# k210-core.net
KiCad netlist of a schematic drawn in Altium Designer
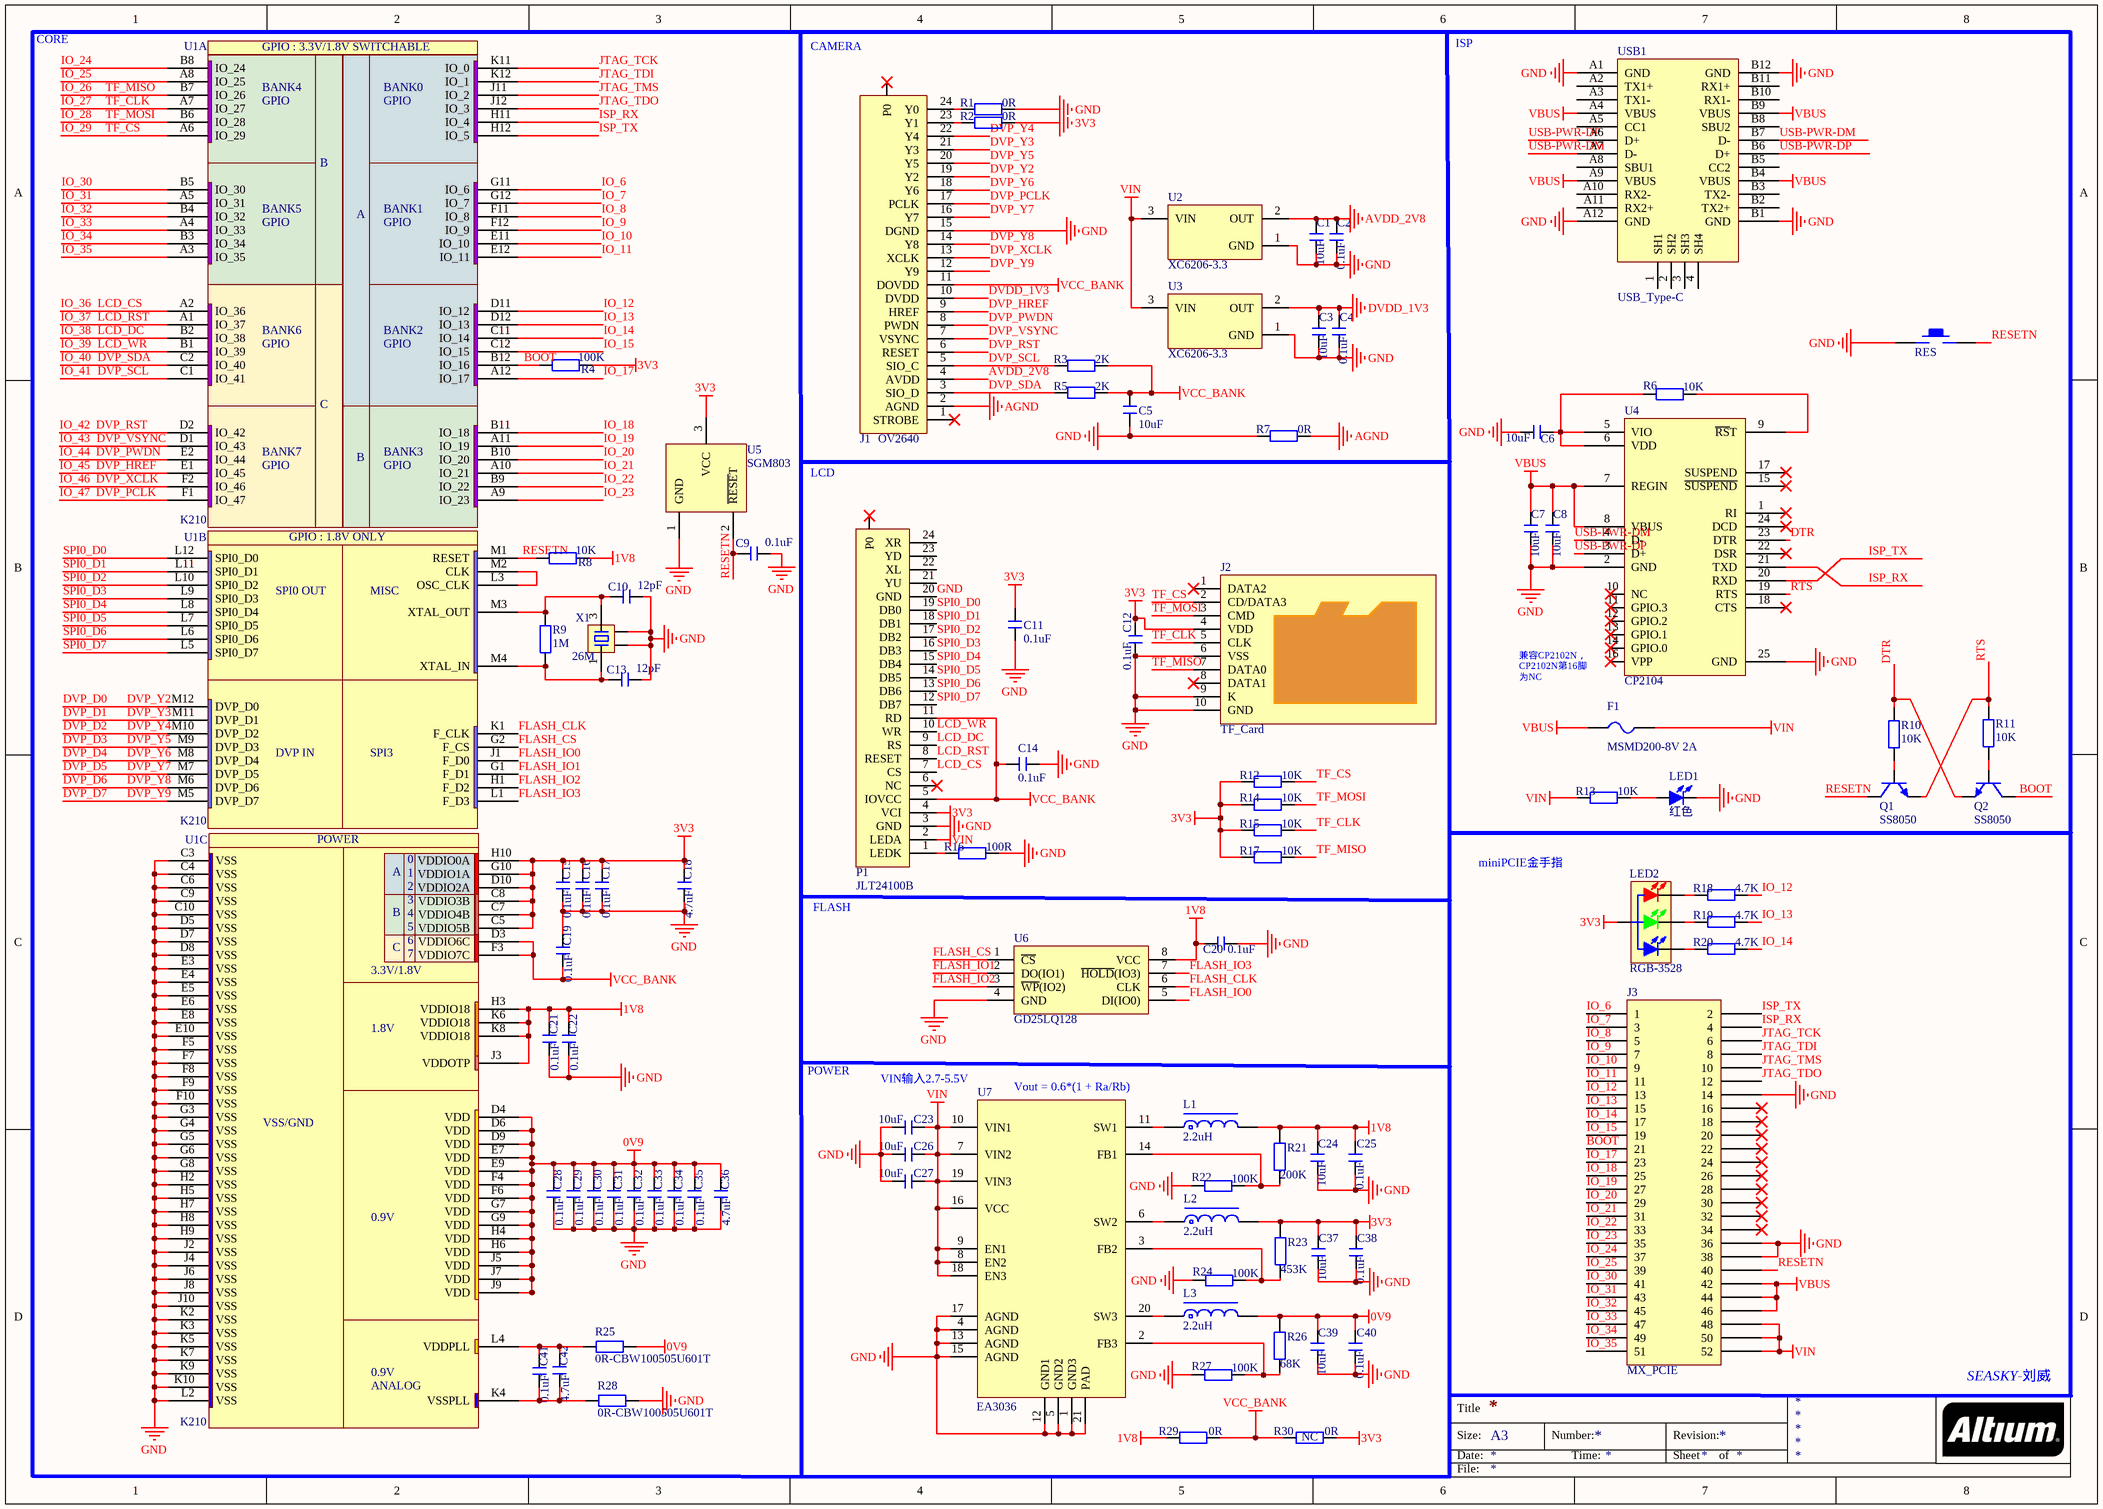
[diagram p0: k210-core.SchDoc]

(export (version "E")
  (design (tool "Eeschema 10.0.6"))
  (components
    (comp (ref "C1")
      (value "10uF")
      (footprint "C 0402_M")
      (description "贴片电容")
      (libsource (lib "0.1 - 电阻-电容-电感") (part "C"))
    )
    (comp (ref "C2")
      (value "0.1uF")
      (footprint "C 0402_M")
      (description "贴片电容")
      (libsource (lib "0.1 - 电阻-电容-电感") (part "C"))
    )
    (comp (ref "C3")
      (value "10uF")
      (footprint "C 0402_M")
      (description "贴片电容")
      (libsource (lib "0.1 - 电阻-电容-电感") (part "C"))
    )
    (comp (ref "C4")
      (value "0.1uF")
      (footprint "C 0402_M")
      (description "贴片电容")
      (libsource (lib "0.1 - 电阻-电容-电感") (part "C"))
    )
    (comp (ref "C5")
      (value "10uF")
      (footprint "C 0402_M")
      (description "贴片电容")
      (libsource (lib "0.1 - 电阻-电容-电感") (part "C"))
    )
    (comp (ref "C6")
      (value "10uF")
      (footprint "C 0402_M")
      (description "贴片电容")
      (libsource (lib "0.1 - 电阻-电容-电感") (part "C"))
    )
    (comp (ref "C7")
      (value "10uF")
      (footprint "C 0402_M")
      (description "贴片电容")
      (libsource (lib "0.1 - 电阻-电容-电感") (part "C"))
    )
    (comp (ref "C8")
      (value "10uF")
      (footprint "C 0402_M")
      (description "贴片电容")
      (libsource (lib "0.1 - 电阻-电容-电感") (part "C"))
    )
    (comp (ref "C9")
      (value "0.1uF")
      (footprint "C 0402_M")
      (description "贴片电容")
      (libsource (lib "0.1 - 电阻-电容-电感") (part "C"))
    )
    (comp (ref "C10")
      (value "12pF")
      (footprint "C 0402_M")
      (description "贴片电容")
      (libsource (lib "0.1 - 电阻-电容-电感") (part "C"))
    )
    (comp (ref "C11")
      (value "0.1uF")
      (footprint "C 0402_M")
      (description "贴片电容")
      (libsource (lib "0.1 - 电阻-电容-电感") (part "C"))
    )
    (comp (ref "C12")
      (value "0.1uF")
      (footprint "C 0402_M")
      (description "贴片电容")
      (libsource (lib "0.1 - 电阻-电容-电感") (part "C"))
    )
    (comp (ref "C13")
      (value "12pF")
      (footprint "C 0402_M")
      (description "贴片电容")
      (libsource (lib "0.1 - 电阻-电容-电感") (part "C"))
    )
    (comp (ref "C14")
      (value "0.1uF")
      (footprint "C 0402_M")
      (description "贴片电容")
      (libsource (lib "0.1 - 电阻-电容-电感") (part "C"))
    )
    (comp (ref "C15")
      (value "0.1uF")
      (footprint "C 0402_M")
      (description "贴片电容")
      (libsource (lib "0.1 - 电阻-电容-电感") (part "C"))
    )
    (comp (ref "C16")
      (value "0.1uF")
      (footprint "C 0402_M")
      (description "贴片电容")
      (libsource (lib "0.1 - 电阻-电容-电感") (part "C"))
    )
    (comp (ref "C17")
      (value "0.1uF")
      (footprint "C 0402_M")
      (description "贴片电容")
      (libsource (lib "0.1 - 电阻-电容-电感") (part "C"))
    )
    (comp (ref "C18")
      (value "4.7uF")
      (footprint "C 0402_M")
      (description "贴片电容")
      (libsource (lib "0.1 - 电阻-电容-电感") (part "C"))
    )
    (comp (ref "C19")
      (value "0.1uF")
      (footprint "C 0402_M")
      (description "贴片电容")
      (libsource (lib "0.1 - 电阻-电容-电感") (part "C"))
    )
    (comp (ref "C20")
      (value "0.1uF")
      (footprint "C 0402_M")
      (description "贴片电容")
      (libsource (lib "0.1 - 电阻-电容-电感") (part "C"))
    )
    (comp (ref "C21")
      (value "0.1uF")
      (footprint "C 0402_M")
      (description "贴片电容")
      (libsource (lib "0.1 - 电阻-电容-电感") (part "C"))
    )
    (comp (ref "C22")
      (value "0.1uF")
      (footprint "C 0402_M")
      (description "贴片电容")
      (libsource (lib "0.1 - 电阻-电容-电感") (part "C"))
    )
    (comp (ref "C23")
      (value "10uF")
      (footprint "C 0402_M")
      (description "贴片电容")
      (libsource (lib "0.1 - 电阻-电容-电感") (part "C"))
    )
    (comp (ref "C24")
      (value "10uF")
      (footprint "C 0402_M")
      (description "贴片电容")
      (libsource (lib "0.1 - 电阻-电容-电感") (part "C"))
    )
    (comp (ref "C25")
      (value "0.1uF")
      (footprint "C 0402_M")
      (description "贴片电容")
      (libsource (lib "0.1 - 电阻-电容-电感") (part "C"))
    )
    (comp (ref "C26")
      (value "10uF")
      (footprint "C 0402_M")
      (description "贴片电容")
      (libsource (lib "0.1 - 电阻-电容-电感") (part "C"))
    )
    (comp (ref "C27")
      (value "10uF")
      (footprint "C 0402_M")
      (description "贴片电容")
      (libsource (lib "0.1 - 电阻-电容-电感") (part "C"))
    )
    (comp (ref "C28")
      (value "0.1uF")
      (footprint "C 0402_M")
      (description "贴片电容")
      (libsource (lib "0.1 - 电阻-电容-电感") (part "C"))
    )
    (comp (ref "C29")
      (value "0.1uF")
      (footprint "C 0402_M")
      (description "贴片电容")
      (libsource (lib "0.1 - 电阻-电容-电感") (part "C"))
    )
    (comp (ref "C30")
      (value "0.1uF")
      (footprint "C 0402_M")
      (description "贴片电容")
      (libsource (lib "0.1 - 电阻-电容-电感") (part "C"))
    )
    (comp (ref "C31")
      (value "0.1uF")
      (footprint "C 0402_M")
      (description "贴片电容")
      (libsource (lib "0.1 - 电阻-电容-电感") (part "C"))
    )
    (comp (ref "C32")
      (value "0.1uF")
      (footprint "C 0402_M")
      (description "贴片电容")
      (libsource (lib "0.1 - 电阻-电容-电感") (part "C"))
    )
    (comp (ref "C33")
      (value "0.1uF")
      (footprint "C 0402_M")
      (description "贴片电容")
      (libsource (lib "0.1 - 电阻-电容-电感") (part "C"))
    )
    (comp (ref "C34")
      (value "0.1uF")
      (footprint "C 0402_M")
      (description "贴片电容")
      (libsource (lib "0.1 - 电阻-电容-电感") (part "C"))
    )
    (comp (ref "C35")
      (value "0.1uF")
      (footprint "C 0402_M")
      (description "贴片电容")
      (libsource (lib "0.1 - 电阻-电容-电感") (part "C"))
    )
    (comp (ref "C36")
      (value "4.7uF")
      (footprint "C 0402_M")
      (description "贴片电容")
      (libsource (lib "0.1 - 电阻-电容-电感") (part "C"))
    )
    (comp (ref "C37")
      (value "10uF")
      (footprint "C 0402_M")
      (description "贴片电容")
      (libsource (lib "0.1 - 电阻-电容-电感") (part "C"))
    )
    (comp (ref "C38")
      (value "0.1uF")
      (footprint "C 0402_M")
      (description "贴片电容")
      (libsource (lib "0.1 - 电阻-电容-电感") (part "C"))
    )
    (comp (ref "C39")
      (value "10uF")
      (footprint "C 0402_M")
      (description "贴片电容")
      (libsource (lib "0.1 - 电阻-电容-电感") (part "C"))
    )
    (comp (ref "C40")
      (value "0.1uF")
      (footprint "C 0402_M")
      (description "贴片电容")
      (libsource (lib "0.1 - 电阻-电容-电感") (part "C"))
    )
    (comp (ref "C41")
      (value "0.1uF")
      (footprint "C 0402_M")
      (description "贴片电容")
      (libsource (lib "0.1 - 电阻-电容-电感") (part "C"))
    )
    (comp (ref "C42")
      (value "4.7uF")
      (footprint "C 0402_M")
      (description "贴片电容")
      (libsource (lib "0.1 - 电阻-电容-电感") (part "C"))
    )
    (comp (ref "F1")
      (value "MSMD200-8V 2A")
      (footprint "FU 1210")
      (description "贴片保险丝")
      (libsource (lib "2.0 - 保险丝-晶振-光耦") (part "FU"))
    )
    (comp (ref "J1")
      (value "OV2640")
      (footprint "FFC/SM0.5-2H24-OV5640")
      (description "Header, 24-Pin")
      (fields (field (name "PUBLISHER") "Altium Limited"))
      (libsource (lib "Vowstar_MCU") (part "OV5640"))
    )
    (comp (ref "J2")
      (value "TF_Card")
      (footprint "TF-SOCKET - short")
      (description "TF卡座")
      (libsource (lib "0.8 - 网口-音频插座") (part "TF_Card"))
    )
    (comp (ref "J3")
      (value "MX_PCIE")
      (footprint "miniPCIE")
      (description "mini-PCI-E")
      (libsource (lib "mx_pcb_library") (part "MX_PCIE"))
    )
    (comp (ref "L1")
      (value "2.2uH")
      (footprint "NR2520")
      (description "NR磁胶电感")
      (libsource (lib "0.1 - 电阻-电容-电感") (part "L-NR"))
    )
    (comp (ref "L2")
      (value "2.2uH")
      (footprint "NR2520")
      (description "NR磁胶电感")
      (libsource (lib "0.1 - 电阻-电容-电感") (part "L-NR"))
    )
    (comp (ref "L3")
      (value "2.2uH")
      (footprint "NR2520")
      (description "NR磁胶电感")
      (libsource (lib "0.1 - 电阻-电容-电感") (part "L-NR"))
    )
    (comp (ref "LED1")
      (value "红色")
      (footprint "LED 0805G")
      (description "贴片LED")
      (libsource (lib "0.3 - LED发光二极管") (part "LED-SMD"))
    )
    (comp (ref "LED2")
      (value "RGB-3528")
      (footprint "LED 3528-4Pin")
      (description "3528三基色LED")
      (libsource (lib "0.3 - LED发光二极管") (part "LED-RGB 3528"))
    )
    (comp (ref "P1")
      (value "JLT24100B")
      (footprint "FFC/SM0.5-2H24-LCD")
      (fields (field (name "PUBLISHER") "Altium Limited"))
      (libsource (lib "Schlib1") (part "JLT24100B"))
    )
    (comp (ref "Q1")
      (value "SS8050")
      (footprint "SOT23-3N")
      (description "高频放大-NPN型")
      (libsource (lib "0.4 - 三极管") (part "8050-SMD"))
    )
    (comp (ref "Q2")
      (value "SS8050")
      (footprint "SOT23-3N")
      (description "高频放大-NPN型")
      (libsource (lib "0.4 - 三极管") (part "8050-SMD"))
    )
    (comp (ref "R1")
      (value "0R")
      (footprint "R 0402_M")
      (description "贴片电阻")
      (libsource (lib "0.1 - 电阻-电容-电感") (part "R"))
    )
    (comp (ref "R2")
      (value "0R")
      (footprint "R 0402_M")
      (description "贴片电阻")
      (libsource (lib "0.1 - 电阻-电容-电感") (part "R"))
    )
    (comp (ref "R3")
      (value "2K")
      (footprint "R 0402_M")
      (description "贴片电阻")
      (libsource (lib "0.1 - 电阻-电容-电感") (part "R"))
    )
    (comp (ref "R4")
      (value "100K")
      (footprint "R 0402_M")
      (description "贴片电阻")
      (libsource (lib "0.1 - 电阻-电容-电感") (part "R"))
    )
    (comp (ref "R5")
      (value "2K")
      (footprint "R 0402_M")
      (description "贴片电阻")
      (libsource (lib "0.1 - 电阻-电容-电感") (part "R"))
    )
    (comp (ref "R6")
      (value "10K")
      (footprint "R 0402_M")
      (description "贴片电阻")
      (libsource (lib "0.1 - 电阻-电容-电感") (part "R"))
    )
    (comp (ref "R7")
      (value "0R")
      (footprint "R 0402_M")
      (description "贴片电阻")
      (libsource (lib "0.1 - 电阻-电容-电感") (part "R"))
    )
    (comp (ref "R8")
      (value "10K")
      (footprint "R 0402_M")
      (description "贴片电阻")
      (libsource (lib "0.1 - 电阻-电容-电感") (part "R"))
    )
    (comp (ref "R9")
      (value "1M")
      (footprint "R 0402_M")
      (description "贴片电阻")
      (libsource (lib "0.1 - 电阻-电容-电感") (part "R"))
    )
    (comp (ref "R10")
      (value "10K")
      (footprint "R 0402_M")
      (description "贴片电阻")
      (libsource (lib "0.1 - 电阻-电容-电感") (part "R"))
    )
    (comp (ref "R11")
      (value "10K")
      (footprint "R 0402_M")
      (description "贴片电阻")
      (libsource (lib "0.1 - 电阻-电容-电感") (part "R"))
    )
    (comp (ref "R12")
      (value "10K")
      (footprint "R 0402_M")
      (description "贴片电阻")
      (libsource (lib "0.1 - 电阻-电容-电感") (part "R"))
    )
    (comp (ref "R13")
      (value "10K")
      (footprint "R 0402_M")
      (description "贴片电阻")
      (libsource (lib "0.1 - 电阻-电容-电感") (part "R"))
    )
    (comp (ref "R14")
      (value "10K")
      (footprint "R 0402_M")
      (description "贴片电阻")
      (libsource (lib "0.1 - 电阻-电容-电感") (part "R"))
    )
    (comp (ref "R15")
      (value "10K")
      (footprint "R 0402_M")
      (description "贴片电阻")
      (libsource (lib "0.1 - 电阻-电容-电感") (part "R"))
    )
    (comp (ref "R16")
      (value "100R")
      (footprint "R 0402_M")
      (description "贴片电阻")
      (libsource (lib "0.1 - 电阻-电容-电感") (part "R"))
    )
    (comp (ref "R17")
      (value "10K")
      (footprint "R 0402_M")
      (description "贴片电阻")
      (libsource (lib "0.1 - 电阻-电容-电感") (part "R"))
    )
    (comp (ref "R18")
      (value "4.7K")
      (footprint "R 0402_M")
      (description "贴片电阻")
      (libsource (lib "0.1 - 电阻-电容-电感") (part "R"))
    )
    (comp (ref "R19")
      (value "4.7K")
      (footprint "R 0402_M")
      (description "贴片电阻")
      (libsource (lib "0.1 - 电阻-电容-电感") (part "R"))
    )
    (comp (ref "R20")
      (value "4.7K")
      (footprint "R 0402_M")
      (description "贴片电阻")
      (libsource (lib "0.1 - 电阻-电容-电感") (part "R"))
    )
    (comp (ref "R21")
      (value "200K")
      (footprint "R 0402_M")
      (description "贴片电阻")
      (libsource (lib "0.1 - 电阻-电容-电感") (part "R"))
    )
    (comp (ref "R22")
      (value "100K")
      (footprint "R 0402_M")
      (description "贴片电阻")
      (libsource (lib "0.1 - 电阻-电容-电感") (part "R"))
    )
    (comp (ref "R23")
      (value "453K")
      (footprint "R 0402_M")
      (description "贴片电阻")
      (libsource (lib "0.1 - 电阻-电容-电感") (part "R"))
    )
    (comp (ref "R24")
      (value "100K")
      (footprint "R 0402_M")
      (description "贴片电阻")
      (libsource (lib "0.1 - 电阻-电容-电感") (part "R"))
    )
    (comp (ref "R25")
      (value "0R-CBW100505U601T")
      (footprint "R 0402_M")
      (description "贴片电阻")
      (libsource (lib "0.1 - 电阻-电容-电感") (part "R"))
    )
    (comp (ref "R26")
      (value "68K")
      (footprint "R 0402_M")
      (description "贴片电阻")
      (libsource (lib "0.1 - 电阻-电容-电感") (part "R"))
    )
    (comp (ref "R27")
      (value "100K")
      (footprint "R 0402_M")
      (description "贴片电阻")
      (libsource (lib "0.1 - 电阻-电容-电感") (part "R"))
    )
    (comp (ref "R28")
      (value "0R-CBW100505U601T")
      (footprint "R 0402_M")
      (description "贴片电阻")
      (libsource (lib "0.1 - 电阻-电容-电感") (part "R"))
    )
    (comp (ref "R29")
      (value "0R")
      (footprint "R 0402_M")
      (description "贴片电阻")
      (libsource (lib "0.1 - 电阻-电容-电感") (part "R"))
    )
    (comp (ref "R30")
      (value "0R")
      (footprint "R 0402_M")
      (description "贴片电阻")
      (libsource (lib "0.1 - 电阻-电容-电感") (part "R"))
    )
    (comp (ref "RST1")
      (value "RES")
      (footprint "mx_pcb_library:SMD-3.2*4.2")
      (libsource (lib "mx_pcb_library") (part "KEY_M"))
    )
    (comp (ref "U1")
      (value "K210")
      (footprint "BGA144C65P12X12_800X800X95")
      (description "Canaan Kendryte K210 AI SoC")
      (libsource (lib "Vowstar_MCU") (part "K210"))
    )
    (comp (ref "U2")
      (value "XC6206-3.3")
      (footprint "2.07-SOT封装:SOT23-3N")
      (description "SOT-23,XC6206P332MR,MAX8V,100mA")
      (libsource (lib "1.1 - 电源类芯片") (part "XC6206-3.3"))
    )
    (comp (ref "U3")
      (value "XC6206-3.3")
      (footprint "2.07-SOT封装:SOT23-3N")
      (description "SOT-23,XC6206P332MR,MAX8V,100mA")
      (libsource (lib "1.1 - 电源类芯片") (part "XC6206-3.3"))
    )
    (comp (ref "U4")
      (value "CP2104")
      (footprint "QFN-24_L4.0-W4.0-P0.50-BL-EP2.8")
      (libsource (lib "Vowstar_MCU") (part "CP2104"))
    )
    (comp (ref "U5")
      (value "SGM803")
      (footprint "2.07-SOT封装:SOT23-3N")
      (libsource (lib "Vowstar_MCU") (part "SGM803"))
    )
    (comp (ref "U6")
      (value "GD25LQ128")
      (footprint "WSON-8_L8.0-W6.10-P1.27-BL-EP")
      (description "WSON-8")
      (libsource (lib "Vowstar_MCU") (part "GD25LQ128"))
    )
    (comp (ref "U7")
      (value "EA3036")
      (footprint "QFN20_40P300X300X80_HS-21N")
      (libsource (lib "Vowstar_MCU") (part "EA3036"))
    )
    (comp (ref "USB1")
      (value "USB_Type-C")
      (footprint "Type-C-TOP")
      (libsource (lib "Vowstar_MCU") (part "USB_Type-C"))
    )
    (comp (ref "X1")
      (value "26M")
      (footprint "OSC 3225-4P")
      (description "4脚无源晶振")
      (libsource (lib "2.0 - 保险丝-晶振-光耦") (part "XTAL-4P"))
    )
  )
  (nets
    (net (code "1") (name "/BOOT") (class "Default")
      (node (ref "J3") (pin "21") (pinfunction "21_21") (pintype "passive"))
      (node (ref "Q2") (pin "3") (pinfunction "C_3") (pintype "passive"))
      (node (ref "R4") (pin "1") (pinfunction "1_1") (pintype "passive"))
      (node (ref "U1") (pin "B12") (pinfunction "IO_16_B12") (pintype "passive"))
    )
    (net (code "2") (name "/DTR") (class "Default")
      (node (ref "Q2") (pin "2") (pinfunction "E_2") (pintype "passive"))
      (node (ref "R10") (pin "1") (pinfunction "1_1") (pintype "passive"))
      (node (ref "U4") (pin "23") (pinfunction "DTR_23") (pintype "passive"))
    )
    (net (code "3") (name "/DVP_D0") (class "Default")
      (node (ref "J1") (pin "19") (pinfunction "Y2_19") (pintype "passive"))
      (node (ref "U1") (pin "M12") (pinfunction "DVP_D0_M12") (pintype "passive"))
    )
    (net (code "4") (name "/DVP_D1") (class "Default")
      (node (ref "J1") (pin "21") (pinfunction "Y3_21") (pintype "passive"))
      (node (ref "U1") (pin "M11") (pinfunction "DVP_D1_M11") (pintype "passive"))
    )
    (net (code "5") (name "/DVP_D2") (class "Default")
      (node (ref "J1") (pin "22") (pinfunction "Y4_22") (pintype "passive"))
      (node (ref "U1") (pin "M10") (pinfunction "DVP_D2_M10") (pintype "passive"))
    )
    (net (code "6") (name "/DVP_D3") (class "Default")
      (node (ref "J1") (pin "20") (pinfunction "Y5_20") (pintype "passive"))
      (node (ref "U1") (pin "M9") (pinfunction "DVP_D3_M9") (pintype "passive"))
    )
    (net (code "7") (name "/DVP_D4") (class "Default")
      (node (ref "J1") (pin "18") (pinfunction "Y6_18") (pintype "passive"))
      (node (ref "U1") (pin "M8") (pinfunction "DVP_D4_M8") (pintype "passive"))
    )
    (net (code "8") (name "/DVP_D5") (class "Default")
      (node (ref "J1") (pin "16") (pinfunction "Y7_16") (pintype "passive"))
      (node (ref "U1") (pin "M7") (pinfunction "DVP_D5_M7") (pintype "passive"))
    )
    (net (code "9") (name "/DVP_D6") (class "Default")
      (node (ref "J1") (pin "14") (pinfunction "Y8_14") (pintype "passive"))
      (node (ref "U1") (pin "M6") (pinfunction "DVP_D6_M6") (pintype "passive"))
    )
    (net (code "10") (name "/DVP_D7") (class "Default")
      (node (ref "J1") (pin "12") (pinfunction "Y9_12") (pintype "passive"))
      (node (ref "U1") (pin "M5") (pinfunction "DVP_D7_M5") (pintype "passive"))
    )
    (net (code "11") (name "/DVP_HREF") (class "Default")
      (node (ref "J1") (pin "9") (pinfunction "HREF_9") (pintype "passive"))
      (node (ref "U1") (pin "E1") (pinfunction "IO_45_E1") (pintype "passive"))
    )
    (net (code "12") (name "/DVP_PCLK") (class "Default")
      (node (ref "J1") (pin "17") (pinfunction "PCLK_17") (pintype "passive"))
      (node (ref "U1") (pin "F1") (pinfunction "IO_47_F1") (pintype "passive"))
    )
    (net (code "13") (name "/DVP_PWDN") (class "Default")
      (node (ref "J1") (pin "8") (pinfunction "PWDN_8") (pintype "passive"))
      (node (ref "U1") (pin "E2") (pinfunction "IO_44_E2") (pintype "passive"))
    )
    (net (code "14") (name "/DVP_RST") (class "Default")
      (node (ref "J1") (pin "6") (pinfunction "RESET_6") (pintype "passive"))
      (node (ref "U1") (pin "D2") (pinfunction "IO_42_D2") (pintype "passive"))
    )
    (net (code "15") (name "/DVP_SCL") (class "Default")
      (node (ref "J1") (pin "5") (pinfunction "SIO_C_5") (pintype "passive"))
      (node (ref "R3") (pin "1") (pinfunction "1_1") (pintype "passive"))
      (node (ref "U1") (pin "C1") (pinfunction "IO_41_C1") (pintype "passive"))
    )
    (net (code "16") (name "/DVP_SDA") (class "Default")
      (node (ref "J1") (pin "3") (pinfunction "SIO_D_3") (pintype "passive"))
      (node (ref "R5") (pin "1") (pinfunction "1_1") (pintype "passive"))
      (node (ref "U1") (pin "C2") (pinfunction "IO_40_C2") (pintype "passive"))
    )
    (net (code "17") (name "/DVP_VSYNC") (class "Default")
      (node (ref "J1") (pin "7") (pinfunction "VSYNC_7") (pintype "passive"))
      (node (ref "U1") (pin "D1") (pinfunction "IO_43_D1") (pintype "passive"))
    )
    (net (code "18") (name "/DVP_XCLK") (class "Default")
      (node (ref "J1") (pin "13") (pinfunction "XCLK_13") (pintype "passive"))
      (node (ref "U1") (pin "F2") (pinfunction "IO_46_F2") (pintype "passive"))
    )
    (net (code "19") (name "/FLASH_CLK") (class "Default")
      (node (ref "U1") (pin "K1") (pinfunction "F_CLK_K1") (pintype "passive"))
      (node (ref "U6") (pin "6") (pinfunction "CLK_6") (pintype "passive"))
    )
    (net (code "20") (name "/FLASH_CS") (class "Default")
      (node (ref "U1") (pin "G2") (pinfunction "F_CS_G2") (pintype "passive"))
      (node (ref "U6") (pin "1") (pinfunction "~{CS}_1") (pintype "passive"))
    )
    (net (code "21") (name "/FLASH_IO0") (class "Default")
      (node (ref "U1") (pin "J1") (pinfunction "F_D0_J1") (pintype "passive"))
      (node (ref "U6") (pin "5") (pinfunction "DI(IO0)_5") (pintype "passive"))
    )
    (net (code "22") (name "/FLASH_IO1") (class "Default")
      (node (ref "U1") (pin "G1") (pinfunction "F_D1_G1") (pintype "passive"))
      (node (ref "U6") (pin "2") (pinfunction "DO(IO1)_2") (pintype "passive"))
    )
    (net (code "23") (name "/FLASH_IO2") (class "Default")
      (node (ref "U1") (pin "H1") (pinfunction "F_D2_H1") (pintype "passive"))
      (node (ref "U6") (pin "3") (pinfunction "~{WP}(IO2)_3") (pintype "passive"))
    )
    (net (code "24") (name "/FLASH_IO3") (class "Default")
      (node (ref "U1") (pin "L1") (pinfunction "F_D3_L1") (pintype "passive"))
      (node (ref "U6") (pin "7") (pinfunction "~{HOLD}(IO3)_7") (pintype "passive"))
    )
    (net (code "25") (name "/IO_6") (class "Default")
      (node (ref "J3") (pin "1") (pinfunction "1_1") (pintype "passive"))
      (node (ref "U1") (pin "G11") (pinfunction "IO_6_G11") (pintype "passive"))
    )
    (net (code "26") (name "/IO_7") (class "Default")
      (node (ref "J3") (pin "3") (pinfunction "3_3") (pintype "passive"))
      (node (ref "U1") (pin "G12") (pinfunction "IO_7_G12") (pintype "passive"))
    )
    (net (code "27") (name "/IO_8") (class "Default")
      (node (ref "J3") (pin "5") (pinfunction "5_5") (pintype "passive"))
      (node (ref "U1") (pin "F11") (pinfunction "IO_8_F11") (pintype "passive"))
    )
    (net (code "28") (name "/IO_9") (class "Default")
      (node (ref "J3") (pin "7") (pinfunction "7_7") (pintype "passive"))
      (node (ref "U1") (pin "F12") (pinfunction "IO_9_F12") (pintype "passive"))
    )
    (net (code "29") (name "/IO_10") (class "Default")
      (node (ref "J3") (pin "9") (pinfunction "9_9") (pintype "passive"))
      (node (ref "U1") (pin "E11") (pinfunction "IO_10_E11") (pintype "passive"))
    )
    (net (code "30") (name "/IO_11") (class "Default")
      (node (ref "J3") (pin "11") (pinfunction "11_11") (pintype "passive"))
      (node (ref "U1") (pin "E12") (pinfunction "IO_11_E12") (pintype "passive"))
    )
    (net (code "31") (name "/IO_12") (class "Default")
      (node (ref "J3") (pin "13") (pinfunction "13_13") (pintype "passive"))
      (node (ref "R18") (pin "2") (pinfunction "2_2") (pintype "passive"))
      (node (ref "U1") (pin "D11") (pinfunction "IO_12_D11") (pintype "passive"))
    )
    (net (code "32") (name "/IO_13") (class "Default")
      (node (ref "J3") (pin "15") (pinfunction "15_15") (pintype "passive"))
      (node (ref "R19") (pin "2") (pinfunction "2_2") (pintype "passive"))
      (node (ref "U1") (pin "D12") (pinfunction "IO_13_D12") (pintype "passive"))
    )
    (net (code "33") (name "/IO_14") (class "Default")
      (node (ref "J3") (pin "17") (pinfunction "17_17") (pintype "passive"))
      (node (ref "R20") (pin "2") (pinfunction "2_2") (pintype "passive"))
      (node (ref "U1") (pin "C11") (pinfunction "IO_14_C11") (pintype "passive"))
    )
    (net (code "34") (name "/IO_15") (class "Default")
      (node (ref "J3") (pin "19") (pinfunction "19_19") (pintype "passive"))
      (node (ref "U1") (pin "C12") (pinfunction "IO_15_C12") (pintype "passive"))
    )
    (net (code "35") (name "/IO_17") (class "Default")
      (node (ref "J3") (pin "23") (pinfunction "23_23") (pintype "passive"))
      (node (ref "U1") (pin "A12") (pinfunction "IO_17_A12") (pintype "passive"))
    )
    (net (code "36") (name "/IO_18") (class "Default")
      (node (ref "J3") (pin "25") (pinfunction "25_25") (pintype "passive"))
      (node (ref "U1") (pin "B11") (pinfunction "IO_18_B11") (pintype "passive"))
    )
    (net (code "37") (name "/IO_19") (class "Default")
      (node (ref "J3") (pin "27") (pinfunction "27_27") (pintype "passive"))
      (node (ref "U1") (pin "A11") (pinfunction "IO_19_A11") (pintype "passive"))
    )
    (net (code "38") (name "/IO_20") (class "Default")
      (node (ref "J3") (pin "29") (pinfunction "29_29") (pintype "passive"))
      (node (ref "U1") (pin "B10") (pinfunction "IO_20_B10") (pintype "passive"))
    )
    (net (code "39") (name "/IO_21") (class "Default")
      (node (ref "J3") (pin "31") (pinfunction "31_31") (pintype "passive"))
      (node (ref "U1") (pin "A10") (pinfunction "IO_21_A10") (pintype "passive"))
    )
    (net (code "40") (name "/IO_22") (class "Default")
      (node (ref "J3") (pin "33") (pinfunction "33_33") (pintype "passive"))
      (node (ref "U1") (pin "B9") (pinfunction "IO_22_B9") (pintype "passive"))
    )
    (net (code "41") (name "/IO_23") (class "Default")
      (node (ref "J3") (pin "35") (pinfunction "35_35") (pintype "passive"))
      (node (ref "U1") (pin "A9") (pinfunction "IO_23_A9") (pintype "passive"))
    )
    (net (code "42") (name "/IO_24") (class "Default")
      (node (ref "J3") (pin "37") (pinfunction "37_37") (pintype "passive"))
      (node (ref "U1") (pin "B8") (pinfunction "IO_24_B8") (pintype "passive"))
    )
    (net (code "43") (name "/IO_25") (class "Default")
      (node (ref "J3") (pin "39") (pinfunction "39_39") (pintype "passive"))
      (node (ref "U1") (pin "A8") (pinfunction "IO_25_A8") (pintype "passive"))
    )
    (net (code "44") (name "/IO_26") (class "Default")
      (node (ref "J2") (pin "7") (pinfunction "DATA0_7") (pintype "passive"))
      (node (ref "R17") (pin "2") (pinfunction "2_2") (pintype "passive"))
      (node (ref "U1") (pin "B7") (pinfunction "IO_26_B7") (pintype "passive"))
    )
    (net (code "45") (name "/IO_27") (class "Default")
      (node (ref "J2") (pin "5") (pinfunction "CLK_5") (pintype "passive"))
      (node (ref "R15") (pin "2") (pinfunction "2_2") (pintype "passive"))
      (node (ref "U1") (pin "A7") (pinfunction "IO_27_A7") (pintype "passive"))
    )
    (net (code "46") (name "/IO_28") (class "Default")
      (node (ref "J2") (pin "3") (pinfunction "CMD_3") (pintype "passive"))
      (node (ref "R14") (pin "2") (pinfunction "2_2") (pintype "passive"))
      (node (ref "U1") (pin "B6") (pinfunction "IO_28_B6") (pintype "passive"))
    )
    (net (code "47") (name "/IO_29") (class "Default")
      (node (ref "J2") (pin "2") (pinfunction "CD/DATA3_2") (pintype "passive"))
      (node (ref "R12") (pin "2") (pinfunction "2_2") (pintype "passive"))
      (node (ref "U1") (pin "A6") (pinfunction "IO_29_A6") (pintype "passive"))
    )
    (net (code "48") (name "/IO_30") (class "Default")
      (node (ref "J3") (pin "41") (pinfunction "41_41") (pintype "passive"))
      (node (ref "U1") (pin "B5") (pinfunction "IO_30_B5") (pintype "passive"))
    )
    (net (code "49") (name "/IO_31") (class "Default")
      (node (ref "J3") (pin "43") (pinfunction "43_43") (pintype "passive"))
      (node (ref "U1") (pin "A5") (pinfunction "IO_31_A5") (pintype "passive"))
    )
    (net (code "50") (name "/IO_32") (class "Default")
      (node (ref "J3") (pin "45") (pinfunction "45_45") (pintype "passive"))
      (node (ref "U1") (pin "B4") (pinfunction "IO_32_B4") (pintype "passive"))
    )
    (net (code "51") (name "/IO_33") (class "Default")
      (node (ref "J3") (pin "47") (pinfunction "47_47") (pintype "passive"))
      (node (ref "U1") (pin "A4") (pinfunction "IO_33_A4") (pintype "passive"))
    )
    (net (code "52") (name "/IO_34") (class "Default")
      (node (ref "J3") (pin "49") (pinfunction "49_49") (pintype "passive"))
      (node (ref "U1") (pin "B3") (pinfunction "IO_34_B3") (pintype "passive"))
    )
    (net (code "53") (name "/IO_35") (class "Default")
      (node (ref "J3") (pin "51") (pinfunction "51_51") (pintype "passive"))
      (node (ref "U1") (pin "A3") (pinfunction "IO_35_A3") (pintype "passive"))
    )
    (net (code "54") (name "/IO_36") (class "Default")
      (node (ref "P1") (pin "7") (pinfunction "CS_7") (pintype "passive"))
      (node (ref "U1") (pin "A2") (pinfunction "IO_36_A2") (pintype "passive"))
    )
    (net (code "55") (name "/IO_37") (class "Default")
      (node (ref "P1") (pin "8") (pinfunction "RESET_8") (pintype "passive"))
      (node (ref "U1") (pin "A1") (pinfunction "IO_37_A1") (pintype "passive"))
    )
    (net (code "56") (name "/IO_38") (class "Default")
      (node (ref "P1") (pin "9") (pinfunction "RS_9") (pintype "passive"))
      (node (ref "U1") (pin "B2") (pinfunction "IO_38_B2") (pintype "passive"))
    )
    (net (code "57") (name "/IO_39") (class "Default")
      (node (ref "P1") (pin "10") (pinfunction "WR_10") (pintype "passive"))
      (node (ref "U1") (pin "B1") (pinfunction "IO_39_B1") (pintype "passive"))
    )
    (net (code "58") (name "/ISP_RX") (class "Default")
      (node (ref "J3") (pin "4") (pinfunction "4_4") (pintype "passive"))
      (node (ref "U1") (pin "H11") (pinfunction "IO_4_H11") (pintype "passive"))
      (node (ref "U4") (pin "21") (pinfunction "TXD_21") (pintype "passive"))
    )
    (net (code "59") (name "/ISP_TX") (class "Default")
      (node (ref "J3") (pin "2") (pinfunction "2_2") (pintype "passive"))
      (node (ref "U1") (pin "H12") (pinfunction "IO_5_H12") (pintype "passive"))
      (node (ref "U4") (pin "20") (pinfunction "RXD_20") (pintype "passive"))
    )
    (net (code "60") (name "/JTAG_TCK") (class "Default")
      (node (ref "J3") (pin "6") (pinfunction "6_6") (pintype "passive"))
      (node (ref "U1") (pin "K11") (pinfunction "IO_0_K11") (pintype "passive"))
    )
    (net (code "61") (name "/JTAG_TDI") (class "Default")
      (node (ref "J3") (pin "8") (pinfunction "8_8") (pintype "passive"))
      (node (ref "U1") (pin "K12") (pinfunction "IO_1_K12") (pintype "passive"))
    )
    (net (code "62") (name "/JTAG_TDO") (class "Default")
      (node (ref "J3") (pin "12") (pinfunction "12_12") (pintype "passive"))
      (node (ref "U1") (pin "J12") (pinfunction "IO_3_J12") (pintype "passive"))
    )
    (net (code "63") (name "/JTAG_TMS") (class "Default")
      (node (ref "J3") (pin "10") (pinfunction "10_10") (pintype "passive"))
      (node (ref "U1") (pin "J11") (pinfunction "IO_2_J11") (pintype "passive"))
    )
    (net (code "64") (name "/RESETN") (class "Default")
      (node (ref "C9") (pin "1") (pinfunction "1_1") (pintype "passive"))
      (node (ref "J3") (pin "40") (pinfunction "40_40") (pintype "passive"))
      (node (ref "Q1") (pin "3") (pinfunction "C_3") (pintype "passive"))
      (node (ref "R8") (pin "1") (pinfunction "1_1") (pintype "passive"))
      (node (ref "RST1") (pin "2") (pinfunction "2_2") (pintype "passive"))
      (node (ref "U1") (pin "M1") (pinfunction "RESET_M1") (pintype "passive"))
      (node (ref "U5") (pin "2") (pinfunction "~{RESE}T_2") (pintype "passive"))
    )
    (net (code "65") (name "/RTS") (class "Default")
      (node (ref "Q1") (pin "2") (pinfunction "E_2") (pintype "passive"))
      (node (ref "R11") (pin "1") (pinfunction "1_1") (pintype "passive"))
      (node (ref "U4") (pin "19") (pinfunction "RTS_19") (pintype "passive"))
    )
    (net (code "66") (name "/SPI0_D0") (class "Default")
      (node (ref "P1") (pin "19") (pinfunction "DB0_19") (pintype "passive"))
      (node (ref "U1") (pin "L12") (pinfunction "SPI0_D0_L12") (pintype "passive"))
    )
    (net (code "67") (name "/SPI0_D1") (class "Default")
      (node (ref "P1") (pin "18") (pinfunction "DB1_18") (pintype "passive"))
      (node (ref "U1") (pin "L11") (pinfunction "SPI0_D1_L11") (pintype "passive"))
    )
    (net (code "68") (name "/SPI0_D2") (class "Default")
      (node (ref "P1") (pin "17") (pinfunction "DB2_17") (pintype "passive"))
      (node (ref "U1") (pin "L10") (pinfunction "SPI0_D2_L10") (pintype "passive"))
    )
    (net (code "69") (name "/SPI0_D3") (class "Default")
      (node (ref "P1") (pin "16") (pinfunction "DB3_16") (pintype "passive"))
      (node (ref "U1") (pin "L9") (pinfunction "SPI0_D3_L9") (pintype "passive"))
    )
    (net (code "70") (name "/SPI0_D4") (class "Default")
      (node (ref "P1") (pin "15") (pinfunction "DB4_15") (pintype "passive"))
      (node (ref "U1") (pin "L8") (pinfunction "SPI0_D4_L8") (pintype "passive"))
    )
    (net (code "71") (name "/SPI0_D5") (class "Default")
      (node (ref "P1") (pin "14") (pinfunction "DB5_14") (pintype "passive"))
      (node (ref "U1") (pin "L7") (pinfunction "SPI0_D5_L7") (pintype "passive"))
    )
    (net (code "72") (name "/SPI0_D6") (class "Default")
      (node (ref "P1") (pin "13") (pinfunction "DB6_13") (pintype "passive"))
      (node (ref "U1") (pin "L6") (pinfunction "SPI0_D6_L6") (pintype "passive"))
    )
    (net (code "73") (name "/SPI0_D7") (class "Default")
      (node (ref "P1") (pin "12") (pinfunction "DB7_12") (pintype "passive"))
      (node (ref "U1") (pin "L5") (pinfunction "SPI0_D7_L5") (pintype "passive"))
    )
    (net (code "74") (name "/USB-PWR-DM") (class "Default")
      (node (ref "U4") (pin "4") (pinfunction "D-_4") (pintype "passive"))
      (node (ref "USB1") (pin "A7") (pinfunction "D-_A7") (pintype "passive"))
      (node (ref "USB1") (pin "B7") (pinfunction "D-_B7") (pintype "passive"))
    )
    (net (code "75") (name "/USB-PWR-DP") (class "Default")
      (node (ref "U4") (pin "3") (pinfunction "D+_3") (pintype "passive"))
      (node (ref "USB1") (pin "A6") (pinfunction "D+_A6") (pintype "passive"))
      (node (ref "USB1") (pin "B6") (pinfunction "D+_B6") (pintype "passive"))
    )
    (net (code "76") (name "0V9") (class "Default")
      (node (ref "C28") (pin "1") (pinfunction "1_1") (pintype "passive"))
      (node (ref "C29") (pin "1") (pinfunction "1_1") (pintype "passive"))
      (node (ref "C30") (pin "1") (pinfunction "1_1") (pintype "passive"))
      (node (ref "C31") (pin "1") (pinfunction "1_1") (pintype "passive"))
      (node (ref "C32") (pin "1") (pinfunction "1_1") (pintype "passive"))
      (node (ref "C33") (pin "1") (pinfunction "1_1") (pintype "passive"))
      (node (ref "C34") (pin "1") (pinfunction "1_1") (pintype "passive"))
      (node (ref "C35") (pin "1") (pinfunction "1_1") (pintype "passive"))
      (node (ref "C36") (pin "1") (pinfunction "1_1") (pintype "passive"))
      (node (ref "C39") (pin "2") (pinfunction "2_2") (pintype "passive"))
      (node (ref "C40") (pin "2") (pinfunction "2_2") (pintype "passive"))
      (node (ref "L3") (pin "2") (pinfunction "2_2") (pintype "passive"))
      (node (ref "R25") (pin "2") (pinfunction "2_2") (pintype "passive"))
      (node (ref "R26") (pin "2") (pinfunction "2_2") (pintype "passive"))
      (node (ref "U1") (pin "D4") (pinfunction "VDD_D4") (pintype "power_in"))
      (node (ref "U1") (pin "D6") (pinfunction "VDD_D6") (pintype "power_in"))
      (node (ref "U1") (pin "D9") (pinfunction "VDD_D9") (pintype "power_in"))
      (node (ref "U1") (pin "E7") (pinfunction "VDD_E7") (pintype "power_in"))
      (node (ref "U1") (pin "E9") (pinfunction "VDD_E9") (pintype "power_in"))
      (node (ref "U1") (pin "F4") (pinfunction "VDD_F4") (pintype "power_in"))
      (node (ref "U1") (pin "F6") (pinfunction "VDD_F6") (pintype "power_in"))
      (node (ref "U1") (pin "G7") (pinfunction "VDD_G7") (pintype "power_in"))
      (node (ref "U1") (pin "G9") (pinfunction "VDD_G9") (pintype "power_in"))
      (node (ref "U1") (pin "H4") (pinfunction "VDD_H4") (pintype "power_in"))
      (node (ref "U1") (pin "H6") (pinfunction "VDD_H6") (pintype "power_in"))
      (node (ref "U1") (pin "J5") (pinfunction "VDD_J5") (pintype "power_in"))
      (node (ref "U1") (pin "J7") (pinfunction "VDD_J7") (pintype "power_in"))
      (node (ref "U1") (pin "J9") (pinfunction "VDD_J9") (pintype "power_in"))
    )
    (net (code "77") (name "1V8") (class "Default")
      (node (ref "C20") (pin "2") (pinfunction "2_2") (pintype "passive"))
      (node (ref "C21") (pin "1") (pinfunction "1_1") (pintype "passive"))
      (node (ref "C22") (pin "1") (pinfunction "1_1") (pintype "passive"))
      (node (ref "C24") (pin "2") (pinfunction "2_2") (pintype "passive"))
      (node (ref "C25") (pin "2") (pinfunction "2_2") (pintype "passive"))
      (node (ref "L1") (pin "2") (pinfunction "2_2") (pintype "passive"))
      (node (ref "R21") (pin "2") (pinfunction "2_2") (pintype "passive"))
      (node (ref "R29") (pin "2") (pinfunction "2_2") (pintype "passive"))
      (node (ref "R8") (pin "2") (pinfunction "2_2") (pintype "passive"))
      (node (ref "U1") (pin "H3") (pinfunction "VDDIO18_H3") (pintype "power_in"))
      (node (ref "U1") (pin "J3") (pinfunction "VDDOTP_J3") (pintype "power_in"))
      (node (ref "U1") (pin "K6") (pinfunction "VDDIO18_K6") (pintype "power_in"))
      (node (ref "U1") (pin "K8") (pinfunction "VDDIO18_K8") (pintype "power_in"))
      (node (ref "U6") (pin "8") (pinfunction "VCC_8") (pintype "passive"))
    )
    (net (code "78") (name "3V3") (class "Default")
      (node (ref "C11") (pin "1") (pinfunction "1_1") (pintype "passive"))
      (node (ref "C12") (pin "1") (pinfunction "1_1") (pintype "passive"))
      (node (ref "C15") (pin "2") (pinfunction "2_2") (pintype "passive"))
      (node (ref "C16") (pin "2") (pinfunction "2_2") (pintype "passive"))
      (node (ref "C17") (pin "2") (pinfunction "2_2") (pintype "passive"))
      (node (ref "C18") (pin "2") (pinfunction "2_2") (pintype "passive"))
      (node (ref "C37") (pin "2") (pinfunction "2_2") (pintype "passive"))
      (node (ref "C38") (pin "2") (pinfunction "2_2") (pintype "passive"))
      (node (ref "J2") (pin "4") (pinfunction "VDD_4") (pintype "passive"))
      (node (ref "L2") (pin "2") (pinfunction "2_2") (pintype "passive"))
      (node (ref "LED2") (pin "4") (pinfunction "A_4") (pintype "passive"))
      (node (ref "P1") (pin "4") (pinfunction "VCI_4") (pintype "passive"))
      (node (ref "R12") (pin "1") (pinfunction "1_1") (pintype "passive"))
      (node (ref "R14") (pin "1") (pinfunction "1_1") (pintype "passive"))
      (node (ref "R15") (pin "1") (pinfunction "1_1") (pintype "passive"))
      (node (ref "R17") (pin "1") (pinfunction "1_1") (pintype "passive"))
      (node (ref "R2") (pin "2") (pinfunction "2_2") (pintype "passive"))
      (node (ref "R23") (pin "2") (pinfunction "2_2") (pintype "passive"))
      (node (ref "R30") (pin "1") (pinfunction "1_1") (pintype "passive"))
      (node (ref "R4") (pin "2") (pinfunction "2_2") (pintype "passive"))
      (node (ref "U1") (pin "C5") (pinfunction "VDDIO5B_C5") (pintype "power_in"))
      (node (ref "U1") (pin "C7") (pinfunction "VDDIO4B_C7") (pintype "power_in"))
      (node (ref "U1") (pin "C8") (pinfunction "VDDIO3B_C8") (pintype "power_in"))
      (node (ref "U1") (pin "D10") (pinfunction "VDDIO2A_D10") (pintype "power_in"))
      (node (ref "U1") (pin "G10") (pinfunction "VDDIO1A_G10") (pintype "power_in"))
      (node (ref "U1") (pin "H10") (pinfunction "VDDIO0A_H10") (pintype "power_in"))
      (node (ref "U5") (pin "3") (pinfunction "VCC_3") (pintype "passive"))
    )
    (net (code "79") (name "AGND") (class "Default")
      (node (ref "J1") (pin "2") (pinfunction "AGND_2") (pintype "passive"))
      (node (ref "R7") (pin "2") (pinfunction "2_2") (pintype "passive"))
    )
    (net (code "80") (name "AVDD_2V8") (class "Default")
      (node (ref "C1") (pin "2") (pinfunction "2_2") (pintype "passive"))
      (node (ref "C2") (pin "2") (pinfunction "2_2") (pintype "passive"))
      (node (ref "J1") (pin "4") (pinfunction "AVDD_4") (pintype "passive"))
      (node (ref "U2") (pin "2") (pinfunction "OUT_2") (pintype "passive"))
    )
    (net (code "81") (name "DVDD_1V3") (class "Default")
      (node (ref "C3") (pin "2") (pinfunction "2_2") (pintype "passive"))
      (node (ref "C4") (pin "2") (pinfunction "2_2") (pintype "passive"))
      (node (ref "J1") (pin "10") (pinfunction "DVDD_10") (pintype "passive"))
      (node (ref "U3") (pin "2") (pinfunction "OUT_2") (pintype "passive"))
    )
    (net (code "82") (name "GND") (class "Default")
      (node (ref "C1") (pin "1") (pinfunction "1_1") (pintype "passive"))
      (node (ref "C10") (pin "2") (pinfunction "2_2") (pintype "passive"))
      (node (ref "C11") (pin "2") (pinfunction "2_2") (pintype "passive"))
      (node (ref "C12") (pin "2") (pinfunction "2_2") (pintype "passive"))
      (node (ref "C13") (pin "2") (pinfunction "2_2") (pintype "passive"))
      (node (ref "C14") (pin "1") (pinfunction "1_1") (pintype "passive"))
      (node (ref "C15") (pin "1") (pinfunction "1_1") (pintype "passive"))
      (node (ref "C16") (pin "1") (pinfunction "1_1") (pintype "passive"))
      (node (ref "C17") (pin "1") (pinfunction "1_1") (pintype "passive"))
      (node (ref "C18") (pin "1") (pinfunction "1_1") (pintype "passive"))
      (node (ref "C19") (pin "1") (pinfunction "1_1") (pintype "passive"))
      (node (ref "C2") (pin "1") (pinfunction "1_1") (pintype "passive"))
      (node (ref "C20") (pin "1") (pinfunction "1_1") (pintype "passive"))
      (node (ref "C21") (pin "2") (pinfunction "2_2") (pintype "passive"))
      (node (ref "C22") (pin "2") (pinfunction "2_2") (pintype "passive"))
      (node (ref "C23") (pin "2") (pinfunction "2_2") (pintype "passive"))
      (node (ref "C24") (pin "1") (pinfunction "1_1") (pintype "passive"))
      (node (ref "C25") (pin "1") (pinfunction "1_1") (pintype "passive"))
      (node (ref "C26") (pin "2") (pinfunction "2_2") (pintype "passive"))
      (node (ref "C27") (pin "2") (pinfunction "2_2") (pintype "passive"))
      (node (ref "C28") (pin "2") (pinfunction "2_2") (pintype "passive"))
      (node (ref "C29") (pin "2") (pinfunction "2_2") (pintype "passive"))
      (node (ref "C3") (pin "1") (pinfunction "1_1") (pintype "passive"))
      (node (ref "C30") (pin "2") (pinfunction "2_2") (pintype "passive"))
      (node (ref "C31") (pin "2") (pinfunction "2_2") (pintype "passive"))
      (node (ref "C32") (pin "2") (pinfunction "2_2") (pintype "passive"))
      (node (ref "C33") (pin "2") (pinfunction "2_2") (pintype "passive"))
      (node (ref "C34") (pin "2") (pinfunction "2_2") (pintype "passive"))
      (node (ref "C35") (pin "2") (pinfunction "2_2") (pintype "passive"))
      (node (ref "C36") (pin "2") (pinfunction "2_2") (pintype "passive"))
      (node (ref "C37") (pin "1") (pinfunction "1_1") (pintype "passive"))
      (node (ref "C38") (pin "1") (pinfunction "1_1") (pintype "passive"))
      (node (ref "C39") (pin "1") (pinfunction "1_1") (pintype "passive"))
      (node (ref "C4") (pin "1") (pinfunction "1_1") (pintype "passive"))
      (node (ref "C40") (pin "1") (pinfunction "1_1") (pintype "passive"))
      (node (ref "C5") (pin "2") (pinfunction "2_2") (pintype "passive"))
      (node (ref "C6") (pin "2") (pinfunction "2_2") (pintype "passive"))
      (node (ref "C7") (pin "1") (pinfunction "1_1") (pintype "passive"))
      (node (ref "C8") (pin "1") (pinfunction "1_1") (pintype "passive"))
      (node (ref "C9") (pin "2") (pinfunction "2_2") (pintype "passive"))
      (node (ref "J1") (pin "15") (pinfunction "DGND_15") (pintype "passive"))
      (node (ref "J2") (pin "10") (pinfunction "GND_10") (pintype "passive"))
      (node (ref "J2") (pin "6") (pinfunction "VSS_6") (pintype "passive"))
      (node (ref "J2") (pin "9") (pinfunction "K_9") (pintype "passive"))
      (node (ref "J3") (pin "14") (pinfunction "14_14") (pintype "passive"))
      (node (ref "J3") (pin "36") (pinfunction "36_36") (pintype "passive"))
      (node (ref "J3") (pin "38") (pinfunction "38_38") (pintype "passive"))
      (node (ref "LED1") (pin "2") (pinfunction "K_2") (pintype "passive"))
      (node (ref "P1") (pin "20") (pinfunction "GND_20") (pintype "passive"))
      (node (ref "P1") (pin "3") (pinfunction "GND_3") (pintype "passive"))
      (node (ref "R1") (pin "2") (pinfunction "2_2") (pintype "passive"))
      (node (ref "R16") (pin "2") (pinfunction "2_2") (pintype "passive"))
      (node (ref "R22") (pin "2") (pinfunction "2_2") (pintype "passive"))
      (node (ref "R24") (pin "2") (pinfunction "2_2") (pintype "passive"))
      (node (ref "R27") (pin "2") (pinfunction "2_2") (pintype "passive"))
      (node (ref "R28") (pin "2") (pinfunction "2_2") (pintype "passive"))
      (node (ref "R7") (pin "1") (pinfunction "1_1") (pintype "passive"))
      (node (ref "RST1") (pin "1") (pinfunction "1_1") (pintype "passive"))
      (node (ref "U1") (pin "C10") (pinfunction "VSS_C10") (pintype "power_in"))
      (node (ref "U1") (pin "C3") (pinfunction "VSS_C3") (pintype "power_in"))
      (node (ref "U1") (pin "C4") (pinfunction "VSS_C4") (pintype "power_in"))
      (node (ref "U1") (pin "C6") (pinfunction "VSS_C6") (pintype "power_in"))
      (node (ref "U1") (pin "C9") (pinfunction "VSS_C9") (pintype "power_in"))
      (node (ref "U1") (pin "D5") (pinfunction "VSS_D5") (pintype "power_in"))
      (node (ref "U1") (pin "D7") (pinfunction "VSS_D7") (pintype "power_in"))
      (node (ref "U1") (pin "D8") (pinfunction "VSS_D8") (pintype "power_in"))
      (node (ref "U1") (pin "E10") (pinfunction "VSS_E10") (pintype "power_in"))
      (node (ref "U1") (pin "E3") (pinfunction "VSS_E3") (pintype "power_in"))
      (node (ref "U1") (pin "E4") (pinfunction "VSS_E4") (pintype "power_in"))
      (node (ref "U1") (pin "E5") (pinfunction "VSS_E5") (pintype "power_in"))
      (node (ref "U1") (pin "E6") (pinfunction "VSS_E6") (pintype "power_in"))
      (node (ref "U1") (pin "E8") (pinfunction "VSS_E8") (pintype "power_in"))
      (node (ref "U1") (pin "F10") (pinfunction "VSS_F10") (pintype "power_in"))
      (node (ref "U1") (pin "F5") (pinfunction "VSS_F5") (pintype "power_in"))
      (node (ref "U1") (pin "F7") (pinfunction "VSS_F7") (pintype "power_in"))
      (node (ref "U1") (pin "F8") (pinfunction "VSS_F8") (pintype "power_in"))
      (node (ref "U1") (pin "F9") (pinfunction "VSS_F9") (pintype "power_in"))
      (node (ref "U1") (pin "G3") (pinfunction "VSS_G3") (pintype "power_in"))
      (node (ref "U1") (pin "G4") (pinfunction "VSS_G4") (pintype "power_in"))
      (node (ref "U1") (pin "G5") (pinfunction "VSS_G5") (pintype "power_in"))
      (node (ref "U1") (pin "G6") (pinfunction "VSS_G6") (pintype "power_in"))
      (node (ref "U1") (pin "G8") (pinfunction "VSS_G8") (pintype "power_in"))
      (node (ref "U1") (pin "H2") (pinfunction "VSS_H2") (pintype "power_in"))
      (node (ref "U1") (pin "H5") (pinfunction "VSS_H5") (pintype "power_in"))
      (node (ref "U1") (pin "H7") (pinfunction "VSS_H7") (pintype "power_in"))
      (node (ref "U1") (pin "H8") (pinfunction "VSS_H8") (pintype "power_in"))
      (node (ref "U1") (pin "H9") (pinfunction "VSS_H9") (pintype "power_in"))
      (node (ref "U1") (pin "J10") (pinfunction "VSS_J10") (pintype "power_in"))
      (node (ref "U1") (pin "J2") (pinfunction "VSS_J2") (pintype "power_in"))
      (node (ref "U1") (pin "J4") (pinfunction "VSS_J4") (pintype "power_in"))
      (node (ref "U1") (pin "J6") (pinfunction "VSS_J6") (pintype "power_in"))
      (node (ref "U1") (pin "J8") (pinfunction "VSS_J8") (pintype "power_in"))
      (node (ref "U1") (pin "K10") (pinfunction "VSS_K10") (pintype "power_in"))
      (node (ref "U1") (pin "K2") (pinfunction "VSS_K2") (pintype "power_in"))
      (node (ref "U1") (pin "K3") (pinfunction "VSS_K3") (pintype "power_in"))
      (node (ref "U1") (pin "K5") (pinfunction "VSS_K5") (pintype "power_in"))
      (node (ref "U1") (pin "K7") (pinfunction "VSS_K7") (pintype "power_in"))
      (node (ref "U1") (pin "K9") (pinfunction "VSS_K9") (pintype "power_in"))
      (node (ref "U1") (pin "L2") (pinfunction "VSS_L2") (pintype "power_in"))
      (node (ref "U2") (pin "1") (pinfunction "GND_1") (pintype "passive"))
      (node (ref "U3") (pin "1") (pinfunction "GND_1") (pintype "passive"))
      (node (ref "U4") (pin "2") (pinfunction "GND_2") (pintype "power_in"))
      (node (ref "U4") (pin "25") (pinfunction "GND_25") (pintype "power_in"))
      (node (ref "U5") (pin "1") (pinfunction "GND_1") (pintype "passive"))
      (node (ref "U6") (pin "4") (pinfunction "GND_4") (pintype "passive"))
      (node (ref "U7") (pin "1") (pinfunction "GND3_1") (pintype "passive"))
      (node (ref "U7") (pin "12") (pinfunction "GND1_12") (pintype "passive"))
      (node (ref "U7") (pin "13") (pinfunction "AGND_13") (pintype "passive"))
      (node (ref "U7") (pin "15") (pinfunction "AGND_15") (pintype "passive"))
      (node (ref "U7") (pin "17") (pinfunction "AGND_17") (pintype "passive"))
      (node (ref "U7") (pin "21") (pinfunction "PAD_21") (pintype "passive"))
      (node (ref "U7") (pin "4") (pinfunction "AGND_4") (pintype "passive"))
      (node (ref "U7") (pin "5") (pinfunction "GND2_5") (pintype "passive"))
      (node (ref "USB1") (pin "A1") (pinfunction "GND_A1") (pintype "passive"))
      (node (ref "USB1") (pin "A12") (pinfunction "GND_A12") (pintype "passive"))
      (node (ref "USB1") (pin "B1") (pinfunction "GND_B1") (pintype "passive"))
      (node (ref "USB1") (pin "B12") (pinfunction "GND_B12") (pintype "passive"))
      (node (ref "X1") (pin "2") (pinfunction "2_2") (pintype "passive"))
      (node (ref "X1") (pin "4") (pinfunction "4_4") (pintype "passive"))
    )
    (net (code "83") (name "Net-(J1-Y0)") (class "Default")
      (node (ref "J1") (pin "24") (pinfunction "Y0_24") (pintype "passive"))
      (node (ref "R1") (pin "1") (pinfunction "1_1") (pintype "passive"))
    )
    (net (code "84") (name "Net-(J1-Y1)") (class "Default")
      (node (ref "J1") (pin "23") (pinfunction "Y1_23") (pintype "passive"))
      (node (ref "R2") (pin "1") (pinfunction "1_1") (pintype "passive"))
    )
    (net (code "85") (name "Net-(LED1-A)") (class "Default")
      (node (ref "LED1") (pin "1") (pinfunction "A_1") (pintype "passive"))
      (node (ref "R13") (pin "2") (pinfunction "2_2") (pintype "passive"))
    )
    (net (code "86") (name "Net-(LED2-BULE_K)") (class "Default")
      (node (ref "LED2") (pin "3") (pinfunction "BULE_K_3") (pintype "passive"))
      (node (ref "R20") (pin "1") (pinfunction "1_1") (pintype "passive"))
    )
    (net (code "87") (name "Net-(LED2-GREEN_K)") (class "Default")
      (node (ref "LED2") (pin "2") (pinfunction "GREEN_K_2") (pintype "passive"))
      (node (ref "R19") (pin "1") (pinfunction "1_1") (pintype "passive"))
    )
    (net (code "88") (name "Net-(LED2-RED_K)") (class "Default")
      (node (ref "LED2") (pin "1") (pinfunction "RED_K_1") (pintype "passive"))
      (node (ref "R18") (pin "1") (pinfunction "1_1") (pintype "passive"))
    )
    (net (code "89") (name "Net-(P1-LEDK)") (class "Default")
      (node (ref "P1") (pin "1") (pinfunction "LEDK_1") (pintype "passive"))
      (node (ref "R16") (pin "1") (pinfunction "1_1") (pintype "passive"))
    )
    (net (code "90") (name "Net-(Q1-B)") (class "Default")
      (node (ref "Q1") (pin "1") (pinfunction "B_1") (pintype "passive"))
      (node (ref "R10") (pin "2") (pinfunction "2_2") (pintype "passive"))
    )
    (net (code "91") (name "Net-(Q2-B)") (class "Default")
      (node (ref "Q2") (pin "1") (pinfunction "B_1") (pintype "passive"))
      (node (ref "R11") (pin "2") (pinfunction "2_2") (pintype "passive"))
    )
    (net (code "92") (name "Net-(U1B-CLK)") (class "Default")
      (node (ref "U1") (pin "L3") (pinfunction "OSC_CLK_L3") (pintype "passive"))
      (node (ref "U1") (pin "M2") (pinfunction "CLK_M2") (pintype "passive"))
    )
    (net (code "93") (name "Net-(U1B-XTAL_IN)") (class "Default")
      (node (ref "C13") (pin "1") (pinfunction "1_1") (pintype "passive"))
      (node (ref "R9") (pin "1") (pinfunction "1_1") (pintype "passive"))
      (node (ref "U1") (pin "M4") (pinfunction "XTAL_IN_M4") (pintype "passive"))
      (node (ref "X1") (pin "1") (pinfunction "1_1") (pintype "passive"))
    )
    (net (code "94") (name "Net-(U1B-XTAL_OUT)") (class "Default")
      (node (ref "C10") (pin "1") (pinfunction "1_1") (pintype "passive"))
      (node (ref "R9") (pin "2") (pinfunction "2_2") (pintype "passive"))
      (node (ref "U1") (pin "M3") (pinfunction "XTAL_OUT_M3") (pintype "passive"))
      (node (ref "X1") (pin "3") (pinfunction "3_3") (pintype "passive"))
    )
    (net (code "95") (name "Net-(U1C-VDDPLL)") (class "Default")
      (node (ref "C41") (pin "1") (pinfunction "1_1") (pintype "passive"))
      (node (ref "C42") (pin "1") (pinfunction "1_1") (pintype "passive"))
      (node (ref "R25") (pin "1") (pinfunction "1_1") (pintype "passive"))
      (node (ref "U1") (pin "L4") (pinfunction "VDDPLL_L4") (pintype "power_in"))
    )
    (net (code "96") (name "Net-(U1C-VSSPLL)") (class "Default")
      (node (ref "C41") (pin "2") (pinfunction "2_2") (pintype "passive"))
      (node (ref "C42") (pin "2") (pinfunction "2_2") (pintype "passive"))
      (node (ref "R28") (pin "1") (pinfunction "1_1") (pintype "passive"))
      (node (ref "U1") (pin "K4") (pinfunction "VSSPLL_K4") (pintype "power_in"))
    )
    (net (code "97") (name "Net-(U4-VDD)") (class "Default")
      (node (ref "C6") (pin "1") (pinfunction "1_1") (pintype "passive"))
      (node (ref "R6") (pin "2") (pinfunction "2_2") (pintype "passive"))
      (node (ref "U4") (pin "5") (pinfunction "VIO_5") (pintype "passive"))
      (node (ref "U4") (pin "6") (pinfunction "VDD_6") (pintype "passive"))
    )
    (net (code "98") (name "Net-(U4-~{RS}T)") (class "Default")
      (node (ref "R6") (pin "1") (pinfunction "1_1") (pintype "passive"))
      (node (ref "U4") (pin "9") (pinfunction "~{RS}T_9") (pintype "passive"))
    )
    (net (code "99") (name "Net-(U7-FB1)") (class "Default")
      (node (ref "R21") (pin "1") (pinfunction "1_1") (pintype "passive"))
      (node (ref "R22") (pin "1") (pinfunction "1_1") (pintype "passive"))
      (node (ref "U7") (pin "14") (pinfunction "FB1_14") (pintype "passive"))
    )
    (net (code "100") (name "Net-(U7-FB2)") (class "Default")
      (node (ref "R23") (pin "1") (pinfunction "1_1") (pintype "passive"))
      (node (ref "R24") (pin "1") (pinfunction "1_1") (pintype "passive"))
      (node (ref "U7") (pin "3") (pinfunction "FB2_3") (pintype "passive"))
    )
    (net (code "101") (name "Net-(U7-FB3)") (class "Default")
      (node (ref "R26") (pin "1") (pinfunction "1_1") (pintype "passive"))
      (node (ref "R27") (pin "1") (pinfunction "1_1") (pintype "passive"))
      (node (ref "U7") (pin "2") (pinfunction "FB3_2") (pintype "passive"))
    )
    (net (code "102") (name "Net-(U7-SW1)") (class "Default")
      (node (ref "L1") (pin "1") (pinfunction "1_1") (pintype "passive"))
      (node (ref "U7") (pin "11") (pinfunction "SW1_11") (pintype "passive"))
    )
    (net (code "103") (name "Net-(U7-SW2)") (class "Default")
      (node (ref "L2") (pin "1") (pinfunction "1_1") (pintype "passive"))
      (node (ref "U7") (pin "6") (pinfunction "SW2_6") (pintype "passive"))
    )
    (net (code "104") (name "Net-(U7-SW3)") (class "Default")
      (node (ref "L3") (pin "1") (pinfunction "1_1") (pintype "passive"))
      (node (ref "U7") (pin "20") (pinfunction "SW3_20") (pintype "passive"))
    )
    (net (code "105") (name "VBUS") (class "Default")
      (node (ref "C7") (pin "2") (pinfunction "2_2") (pintype "passive"))
      (node (ref "C8") (pin "2") (pinfunction "2_2") (pintype "passive"))
      (node (ref "F1") (pin "1") (pinfunction "1_1") (pintype "passive"))
      (node (ref "J3") (pin "42") (pinfunction "42_42") (pintype "passive"))
      (node (ref "J3") (pin "44") (pinfunction "44_44") (pintype "passive"))
      (node (ref "J3") (pin "46") (pinfunction "46_46") (pintype "passive"))
      (node (ref "U4") (pin "7") (pinfunction "REGIN_7") (pintype "passive"))
      (node (ref "U4") (pin "8") (pinfunction "VBUS_8") (pintype "power_in"))
      (node (ref "USB1") (pin "A4") (pinfunction "VBUS_A4") (pintype "passive"))
      (node (ref "USB1") (pin "A9") (pinfunction "VBUS_A9") (pintype "passive"))
      (node (ref "USB1") (pin "B4") (pinfunction "VBUS_B4") (pintype "passive"))
      (node (ref "USB1") (pin "B9") (pinfunction "VBUS_B9") (pintype "passive"))
    )
    (net (code "106") (name "VCC_BANK") (class "Default")
      (node (ref "C14") (pin "2") (pinfunction "2_2") (pintype "passive"))
      (node (ref "C19") (pin "2") (pinfunction "2_2") (pintype "passive"))
      (node (ref "C5") (pin "1") (pinfunction "1_1") (pintype "passive"))
      (node (ref "J1") (pin "11") (pinfunction "DOVDD_11") (pintype "passive"))
      (node (ref "P1") (pin "11") (pinfunction "RD_11") (pintype "passive"))
      (node (ref "P1") (pin "5") (pinfunction "IOVCC_5") (pintype "passive"))
      (node (ref "R29") (pin "1") (pinfunction "1_1") (pintype "passive"))
      (node (ref "R3") (pin "2") (pinfunction "2_2") (pintype "passive"))
      (node (ref "R30") (pin "2") (pinfunction "2_2") (pintype "passive"))
      (node (ref "R5") (pin "2") (pinfunction "2_2") (pintype "passive"))
      (node (ref "U1") (pin "D3") (pinfunction "VDDIO6C_D3") (pintype "power_in"))
      (node (ref "U1") (pin "F3") (pinfunction "VDDIO7C_F3") (pintype "power_in"))
    )
    (net (code "107") (name "VIN") (class "Default")
      (node (ref "C23") (pin "1") (pinfunction "1_1") (pintype "passive"))
      (node (ref "C26") (pin "1") (pinfunction "1_1") (pintype "passive"))
      (node (ref "C27") (pin "1") (pinfunction "1_1") (pintype "passive"))
      (node (ref "F1") (pin "2") (pinfunction "2_2") (pintype "passive"))
      (node (ref "J3") (pin "48") (pinfunction "48_48") (pintype "passive"))
      (node (ref "J3") (pin "50") (pinfunction "50_50") (pintype "passive"))
      (node (ref "J3") (pin "52") (pinfunction "52_52") (pintype "passive"))
      (node (ref "P1") (pin "2") (pinfunction "LEDA_2") (pintype "passive"))
      (node (ref "R13") (pin "1") (pinfunction "1_1") (pintype "passive"))
      (node (ref "U2") (pin "3") (pinfunction "VIN_3") (pintype "passive"))
      (node (ref "U3") (pin "3") (pinfunction "VIN_3") (pintype "passive"))
      (node (ref "U7") (pin "10") (pinfunction "VIN1_10") (pintype "passive"))
      (node (ref "U7") (pin "16") (pinfunction "VCC_16") (pintype "passive"))
      (node (ref "U7") (pin "18") (pinfunction "EN3_18") (pintype "passive"))
      (node (ref "U7") (pin "19") (pinfunction "VIN3_19") (pintype "passive"))
      (node (ref "U7") (pin "7") (pinfunction "VIN2_7") (pintype "passive"))
      (node (ref "U7") (pin "8") (pinfunction "EN2_8") (pintype "passive"))
      (node (ref "U7") (pin "9") (pinfunction "EN1_9") (pintype "passive"))
    )
    (net (code "108") (name "unconnected-(J1-PadP0)") (class "Default")
      (node (ref "J1") (pin "P0") (pinfunction "P0_P0") (pintype "passive+no_connect"))
    )
    (net (code "109") (name "unconnected-(J1-STROBE-Pad1)") (class "Default")
      (node (ref "J1") (pin "1") (pinfunction "STROBE_1") (pintype "passive+no_connect"))
    )
    (net (code "110") (name "unconnected-(J2-DATA1-Pad8)") (class "Default")
      (node (ref "J2") (pin "8") (pinfunction "DATA1_8") (pintype "passive+no_connect"))
    )
    (net (code "111") (name "unconnected-(J2-DATA2-Pad1)") (class "Default")
      (node (ref "J2") (pin "1") (pinfunction "DATA2_1") (pintype "passive+no_connect"))
    )
    (net (code "112") (name "unconnected-(J3-Pad16)") (class "Default")
      (node (ref "J3") (pin "16") (pinfunction "16_16") (pintype "passive+no_connect"))
    )
    (net (code "113") (name "unconnected-(J3-Pad18)") (class "Default")
      (node (ref "J3") (pin "18") (pinfunction "18_18") (pintype "passive+no_connect"))
    )
    (net (code "114") (name "unconnected-(J3-Pad20)") (class "Default")
      (node (ref "J3") (pin "20") (pinfunction "20_20") (pintype "passive+no_connect"))
    )
    (net (code "115") (name "unconnected-(J3-Pad22)") (class "Default")
      (node (ref "J3") (pin "22") (pinfunction "22_22") (pintype "passive+no_connect"))
    )
    (net (code "116") (name "unconnected-(J3-Pad24)") (class "Default")
      (node (ref "J3") (pin "24") (pinfunction "24_24") (pintype "passive+no_connect"))
    )
    (net (code "117") (name "unconnected-(J3-Pad26)") (class "Default")
      (node (ref "J3") (pin "26") (pinfunction "26_26") (pintype "passive+no_connect"))
    )
    (net (code "118") (name "unconnected-(J3-Pad28)") (class "Default")
      (node (ref "J3") (pin "28") (pinfunction "28_28") (pintype "passive+no_connect"))
    )
    (net (code "119") (name "unconnected-(J3-Pad30)") (class "Default")
      (node (ref "J3") (pin "30") (pinfunction "30_30") (pintype "passive+no_connect"))
    )
    (net (code "120") (name "unconnected-(J3-Pad32)") (class "Default")
      (node (ref "J3") (pin "32") (pinfunction "32_32") (pintype "passive+no_connect"))
    )
    (net (code "121") (name "unconnected-(J3-Pad34)") (class "Default")
      (node (ref "J3") (pin "34") (pinfunction "34_34") (pintype "passive+no_connect"))
    )
    (net (code "122") (name "unconnected-(P1-NC-Pad6)") (class "Default")
      (node (ref "P1") (pin "6") (pinfunction "NC_6") (pintype "passive+no_connect"))
    )
    (net (code "123") (name "unconnected-(P1-PadP0)") (class "Default")
      (node (ref "P1") (pin "P0") (pinfunction "P0_P0") (pintype "passive+no_connect"))
    )
    (net (code "124") (name "unconnected-(P1-XL-Pad22)") (class "Default")
      (node (ref "P1") (pin "22") (pinfunction "XL_22") (pintype "passive"))
    )
    (net (code "125") (name "unconnected-(P1-XR-Pad24)") (class "Default")
      (node (ref "P1") (pin "24") (pinfunction "XR_24") (pintype "passive"))
    )
    (net (code "126") (name "unconnected-(P1-YD-Pad23)") (class "Default")
      (node (ref "P1") (pin "23") (pinfunction "YD_23") (pintype "passive"))
    )
    (net (code "127") (name "unconnected-(P1-YU-Pad21)") (class "Default")
      (node (ref "P1") (pin "21") (pinfunction "YU_21") (pintype "passive"))
    )
    (net (code "128") (name "unconnected-(U4-CTS-Pad18)") (class "Default")
      (node (ref "U4") (pin "18") (pinfunction "CTS_18") (pintype "passive+no_connect"))
    )
    (net (code "129") (name "unconnected-(U4-DCD-Pad24)") (class "Default")
      (node (ref "U4") (pin "24") (pinfunction "DCD_24") (pintype "passive+no_connect"))
    )
    (net (code "130") (name "unconnected-(U4-DSR-Pad22)") (class "Default")
      (node (ref "U4") (pin "22") (pinfunction "DSR_22") (pintype "passive+no_connect"))
    )
    (net (code "131") (name "unconnected-(U4-GPIO.0-Pad14)") (class "Default")
      (node (ref "U4") (pin "14") (pinfunction "GPIO.0_14") (pintype "passive+no_connect"))
    )
    (net (code "132") (name "unconnected-(U4-GPIO.1-Pad13)") (class "Default")
      (node (ref "U4") (pin "13") (pinfunction "GPIO.1_13") (pintype "passive+no_connect"))
    )
    (net (code "133") (name "unconnected-(U4-GPIO.2-Pad12)") (class "Default")
      (node (ref "U4") (pin "12") (pinfunction "GPIO.2_12") (pintype "passive+no_connect"))
    )
    (net (code "134") (name "unconnected-(U4-GPIO.3-Pad11)") (class "Default")
      (node (ref "U4") (pin "11") (pinfunction "GPIO.3_11") (pintype "passive+no_connect"))
    )
    (net (code "135") (name "unconnected-(U4-NC-Pad10)") (class "Default")
      (node (ref "U4") (pin "10") (pinfunction "NC_10") (pintype "passive+no_connect"))
    )
    (net (code "136") (name "unconnected-(U4-RI-Pad1)") (class "Default")
      (node (ref "U4") (pin "1") (pinfunction "RI_1") (pintype "passive+no_connect"))
    )
    (net (code "137") (name "unconnected-(U4-SUSPEND-Pad17)") (class "Default")
      (node (ref "U4") (pin "17") (pinfunction "SUSPEND_17") (pintype "passive+no_connect"))
    )
    (net (code "138") (name "unconnected-(U4-VPP-Pad16)") (class "Default")
      (node (ref "U4") (pin "16") (pinfunction "VPP_16") (pintype "passive+no_connect"))
    )
    (net (code "139") (name "unconnected-(U4-~{SUSPEND}-Pad15)") (class "Default")
      (node (ref "U4") (pin "15") (pinfunction "~{SUSPEND}_15") (pintype "passive+no_connect"))
    )
    (net (code "140") (name "unconnected-(USB1-CC1-PadA5)") (class "Default")
      (node (ref "USB1") (pin "A5") (pinfunction "CC1_A5") (pintype "passive"))
    )
    (net (code "141") (name "unconnected-(USB1-CC2-PadB5)") (class "Default")
      (node (ref "USB1") (pin "B5") (pinfunction "CC2_B5") (pintype "passive"))
    )
    (net (code "142") (name "unconnected-(USB1-RX1+-PadB11)") (class "Default")
      (node (ref "USB1") (pin "B11") (pinfunction "RX1+_B11") (pintype "passive"))
    )
    (net (code "143") (name "unconnected-(USB1-RX1--PadB10)") (class "Default")
      (node (ref "USB1") (pin "B10") (pinfunction "RX1-_B10") (pintype "passive"))
    )
    (net (code "144") (name "unconnected-(USB1-RX2+-PadA11)") (class "Default")
      (node (ref "USB1") (pin "A11") (pinfunction "RX2+_A11") (pintype "passive"))
    )
    (net (code "145") (name "unconnected-(USB1-RX2--PadA10)") (class "Default")
      (node (ref "USB1") (pin "A10") (pinfunction "RX2-_A10") (pintype "passive"))
    )
    (net (code "146") (name "unconnected-(USB1-SBU1-PadA8)") (class "Default")
      (node (ref "USB1") (pin "A8") (pinfunction "SBU1_A8") (pintype "passive"))
    )
    (net (code "147") (name "unconnected-(USB1-SBU2-PadB8)") (class "Default")
      (node (ref "USB1") (pin "B8") (pinfunction "SBU2_B8") (pintype "passive"))
    )
    (net (code "148") (name "unconnected-(USB1-SH1-Pad1)") (class "Default")
      (node (ref "USB1") (pin "1") (pinfunction "SH1_1") (pintype "passive"))
    )
    (net (code "149") (name "unconnected-(USB1-SH2-Pad2)") (class "Default")
      (node (ref "USB1") (pin "2") (pinfunction "SH2_2") (pintype "passive"))
    )
    (net (code "150") (name "unconnected-(USB1-SH3-Pad3)") (class "Default")
      (node (ref "USB1") (pin "3") (pinfunction "SH3_3") (pintype "passive"))
    )
    (net (code "151") (name "unconnected-(USB1-SH4-Pad4)") (class "Default")
      (node (ref "USB1") (pin "4") (pinfunction "SH4_4") (pintype "passive"))
    )
    (net (code "152") (name "unconnected-(USB1-TX1+-PadA2)") (class "Default")
      (node (ref "USB1") (pin "A2") (pinfunction "TX1+_A2") (pintype "passive"))
    )
    (net (code "153") (name "unconnected-(USB1-TX1--PadA3)") (class "Default")
      (node (ref "USB1") (pin "A3") (pinfunction "TX1-_A3") (pintype "passive"))
    )
    (net (code "154") (name "unconnected-(USB1-TX2+-PadB2)") (class "Default")
      (node (ref "USB1") (pin "B2") (pinfunction "TX2+_B2") (pintype "passive"))
    )
    (net (code "155") (name "unconnected-(USB1-TX2--PadB3)") (class "Default")
      (node (ref "USB1") (pin "B3") (pinfunction "TX2-_B3") (pintype "passive"))
    )
  )
)
